# V1.net
KiCad netlist of a schematic drawn in EAGLE
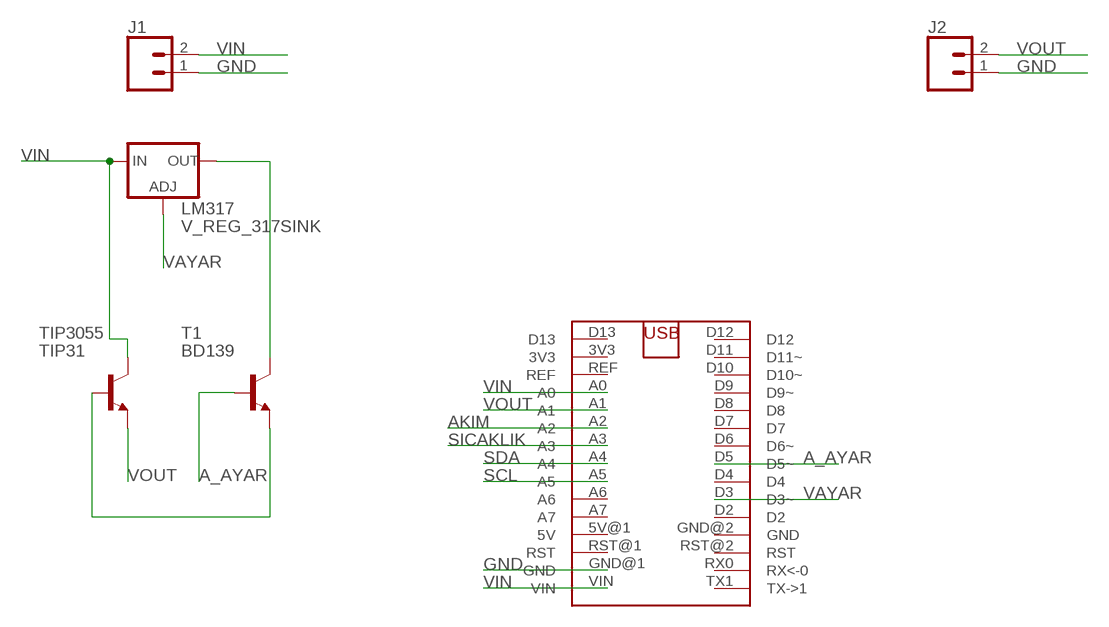
[diagram p0: schematic, sheet 1]

(export (version "E")
  (design (tool "Eeschema 10.0.6"))
  (components
    (comp (ref "J1")
      (value "CONN_021X02_NO_SILK")
      (footprint "eagle-import:1X02_NO_SILK")
      (libsource (lib "eagle-import") (part "CONN_021X02_NO_SILK"))
    )
    (comp (ref "J2")
      (value "CONN_021X02_NO_SILK")
      (footprint "eagle-import:1X02_NO_SILK")
      (libsource (lib "eagle-import") (part "CONN_021X02_NO_SILK"))
    )
    (comp (ref "LM317")
      (value "V_REG_317SINK")
      (footprint "eagle-import:TO220-ADJ")
      (libsource (lib "eagle-import") (part "V_REG_317SINK"))
    )
    (comp (ref "T1")
      (value "BD139")
      (footprint "eagle-import:TO126")
      (libsource (lib "eagle-import") (part "BD139"))
    )
    (comp (ref "TIP3055")
      (value "TIP31")
      (footprint "eagle-import:TO220")
      (libsource (lib "eagle-import") (part "TIP31"))
    )
    (comp (ref "U$1")
      (value "ARDUINO_NANO")
      (footprint "eagle-import:ARDUINO_NANO")
      (libsource (lib "eagle-import") (part "ARDUINO_NANO"))
    )
  )
  (nets
    (net (code "1") (name "/AKIM") (class "Default")
      (node (ref "U$1") (pin "A2") (pinfunction "A2_A2") (pintype "bidirectional"))
    )
    (net (code "2") (name "/A_AYAR") (class "Default")
      (node (ref "T1") (pin "3") (pinfunction "B_3") (pintype "passive"))
      (node (ref "U$1") (pin "D5") (pinfunction "D5~{}_D5") (pintype "bidirectional"))
    )
    (net (code "3") (name "/GND") (class "Default")
      (node (ref "J1") (pin "1") (pinfunction "1_1") (pintype "passive"))
      (node (ref "J2") (pin "1") (pinfunction "1_1") (pintype "passive"))
      (node (ref "U$1") (pin "GND@1") (pinfunction "GND_GND@1") (pintype "bidirectional"))
    )
    (net (code "4") (name "/SCL") (class "Default")
      (node (ref "U$1") (pin "A5") (pinfunction "A5_A5") (pintype "bidirectional"))
    )
    (net (code "5") (name "/SDA") (class "Default")
      (node (ref "U$1") (pin "A4") (pinfunction "A4_A4") (pintype "bidirectional"))
    )
    (net (code "6") (name "/SICAKLIK") (class "Default")
      (node (ref "U$1") (pin "A3") (pinfunction "A3_A3") (pintype "bidirectional"))
    )
    (net (code "7") (name "/VAYAR") (class "Default")
      (node (ref "LM317") (pin "ADJ") (pinfunction "ADJ_ADJ") (pintype "input"))
      (node (ref "U$1") (pin "D3") (pinfunction "D3~{}_D3") (pintype "bidirectional"))
    )
    (net (code "8") (name "/VIN") (class "Default")
      (node (ref "J1") (pin "2") (pinfunction "2_2") (pintype "passive"))
      (node (ref "LM317") (pin "IN") (pinfunction "IN_IN") (pintype "input"))
      (node (ref "TIP3055") (pin "2") (pinfunction "C_2") (pintype "passive"))
      (node (ref "U$1") (pin "A0") (pinfunction "A0_A0") (pintype "bidirectional"))
      (node (ref "U$1") (pin "VIN") (pinfunction "VIN_VIN") (pintype "bidirectional"))
    )
    (net (code "9") (name "/VOUT") (class "Default")
      (node (ref "J2") (pin "2") (pinfunction "2_2") (pintype "passive"))
      (node (ref "LM317") (pin "OUT") (pinfunction "OUT_OUT") (pintype "output"))
      (node (ref "T1") (pin "2") (pinfunction "C_2") (pintype "passive"))
      (node (ref "TIP3055") (pin "3") (pinfunction "E_3") (pintype "passive"))
      (node (ref "U$1") (pin "A1") (pinfunction "A1_A1") (pintype "bidirectional"))
    )
    (net (code "10") (name "Net-(T1-E)") (class "Default")
      (node (ref "T1") (pin "1") (pinfunction "E_1") (pintype "passive"))
      (node (ref "TIP3055") (pin "1") (pinfunction "B_1") (pintype "passive"))
    )
    (net (code "11") (name "unconnected-(U$1-5V-Pad5V@1)") (class "Default")
      (node (ref "U$1") (pin "5V@1") (pinfunction "5V_5V@1") (pintype "bidirectional"))
    )
    (net (code "12") (name "unconnected-(U$1-D6~{}-PadD6)") (class "Default")
      (node (ref "U$1") (pin "D6") (pinfunction "D6~{}_D6") (pintype "bidirectional"))
    )
    (net (code "13") (name "unconnected-(U$1-D9~{}-PadD9)") (class "Default")
      (node (ref "U$1") (pin "D9") (pinfunction "D9~{}_D9") (pintype "bidirectional"))
    )
    (net (code "14") (name "unconnected-(U$1-D10~{}-PadD10)") (class "Default")
      (node (ref "U$1") (pin "D10") (pinfunction "D10~{}_D10") (pintype "bidirectional"))
    )
    (net (code "15") (name "unconnected-(U$1-D11~{}-PadD11)") (class "Default")
      (node (ref "U$1") (pin "D11") (pinfunction "D11~{}_D11") (pintype "bidirectional"))
    )
    (net (code "16") (name "unconnected-(U$1-GND-PadGND@2)") (class "Default")
      (node (ref "U$1") (pin "GND@2") (pinfunction "GND_GND@2") (pintype "bidirectional"))
    )
    (net (code "17") (name "unconnected-(U$1-Pad3V3)") (class "Default")
      (node (ref "U$1") (pin "3V3") (pinfunction "3V3_3V3") (pintype "bidirectional"))
    )
    (net (code "18") (name "unconnected-(U$1-PadA6)") (class "Default")
      (node (ref "U$1") (pin "A6") (pinfunction "A6_A6") (pintype "bidirectional"))
    )
    (net (code "19") (name "unconnected-(U$1-PadA7)") (class "Default")
      (node (ref "U$1") (pin "A7") (pinfunction "A7_A7") (pintype "bidirectional"))
    )
    (net (code "20") (name "unconnected-(U$1-PadD2)") (class "Default")
      (node (ref "U$1") (pin "D2") (pinfunction "D2_D2") (pintype "bidirectional"))
    )
    (net (code "21") (name "unconnected-(U$1-PadD4)") (class "Default")
      (node (ref "U$1") (pin "D4") (pinfunction "D4_D4") (pintype "bidirectional"))
    )
    (net (code "22") (name "unconnected-(U$1-PadD7)") (class "Default")
      (node (ref "U$1") (pin "D7") (pinfunction "D7_D7") (pintype "bidirectional"))
    )
    (net (code "23") (name "unconnected-(U$1-PadD8)") (class "Default")
      (node (ref "U$1") (pin "D8") (pinfunction "D8_D8") (pintype "bidirectional"))
    )
    (net (code "24") (name "unconnected-(U$1-PadD12)") (class "Default")
      (node (ref "U$1") (pin "D12") (pinfunction "D12_D12") (pintype "bidirectional"))
    )
    (net (code "25") (name "unconnected-(U$1-PadD13)") (class "Default")
      (node (ref "U$1") (pin "D13") (pinfunction "D13_D13") (pintype "bidirectional"))
    )
    (net (code "26") (name "unconnected-(U$1-PadREF)") (class "Default")
      (node (ref "U$1") (pin "REF") (pinfunction "REF_REF") (pintype "bidirectional"))
    )
    (net (code "27") (name "unconnected-(U$1-RST-PadRST@1)") (class "Default")
      (node (ref "U$1") (pin "RST@1") (pinfunction "RST_RST@1") (pintype "bidirectional"))
    )
    (net (code "28") (name "unconnected-(U$1-RST-PadRST@2)") (class "Default")
      (node (ref "U$1") (pin "RST@2") (pinfunction "RST_RST@2") (pintype "bidirectional"))
    )
    (net (code "29") (name "unconnected-(U$1-RX<-0-PadRX0)") (class "Default")
      (node (ref "U$1") (pin "RX0") (pinfunction "RX<-0_RX0") (pintype "bidirectional"))
    )
    (net (code "30") (name "unconnected-(U$1-TX->1-PadTX1)") (class "Default")
      (node (ref "U$1") (pin "TX1") (pinfunction "TX->1_TX1") (pintype "bidirectional"))
    )
  )
)
